# Sheet2.net
KiCad netlist of a schematic drawn in Altium Designer
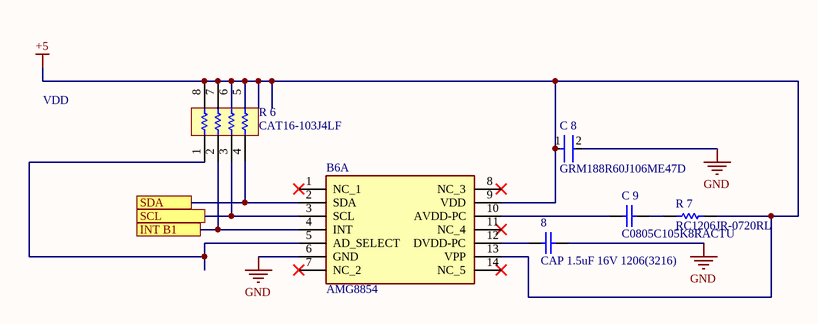
[diagram p0: Sheet2.SchDoc]

(export (version "E")
  (design (tool "Eeschema 10.0.6"))
  (components
    (comp (ref "8")
      (value "CAP 1.5uF 16V 1206(3216)")
      (footprint "CAPC1206(3216)190_M")
      (description "CAP 1.5uF 16V ±10% 1206 (3216 Metric) Thickness 1.9mm SMD")
      (fields (field (name "TOLERANCE") "Â±10%"))
      (libsource (lib "Altium Content Vault") (part "CAP"))
    )
    (comp (ref "B6")
      (value "AMG8854")
      (footprint "AMG8854:AMG8854")
      (fields (field (name "MOUSER PART NUMBER") "667-AMG8854"))
      (libsource (lib "AMG8854") (part "AMG8854"))
    )
    (comp (ref "C 8")
      (value "GRM188R60J106ME47D")
      (footprint "FP-GRM188-0_1-e0_2_0_55-IPC_A")
      (description "Chip Multilayer Ceramic Capacitors for General Purpose, 0603, 10uF, X5R, 15%, 20%, 6.3V")
      (fields (field (name "VOLTAGE") "6.3V") (field (name "TOLERANCE") "20%"))
      (libsource (lib "Altium Content Vault") (part "02cd4be3c70576c341d710602a673aa"))
    )
    (comp (ref "C 9")
      (value "C0805C105K8RACTU")
      (footprint "CAPC2013X100X50ML20T25")
      (fields (field (name "MANUFACTURER") "Kemet"))
      (libsource (lib "Altium Content Vault") (part "CAP"))
    )
    (comp (ref "R 6")
      (value "CAT16-103J4LF")
      (footprint "BOUR-CAT16-103J4LF_L")
      (fields (field (name "MANUFACTURER") "Bourns") (field (name "TOLERANCE") "±5%"))
      (libsource (lib "Altium Content Vault") (part "RES-P-8"))
    )
    (comp (ref "R 7")
      (value "RC1206JR-0720RL")
      (footprint "RESC3116X65X40NL10T20")
      (fields (field (name "MANUFACTURER") "Yageo"))
      (libsource (lib "Altium Content Vault") (part "RES"))
    )
  )
  (nets
    (net (code "1") (name "+5") (class "Default")
      (node (ref "B6") (pin "13") (pinfunction "VPP_13") (pintype "passive"))
      (node (ref "B6") (pin "9") (pinfunction "VDD_9") (pintype "passive"))
      (node (ref "C 8") (pin "1") (pinfunction "1_1") (pintype "passive"))
      (node (ref "R 6") (pin "5") (pinfunction "5_5") (pintype "passive"))
      (node (ref "R 6") (pin "6") (pinfunction "6_6") (pintype "passive"))
      (node (ref "R 6") (pin "7") (pinfunction "7_7") (pintype "passive"))
      (node (ref "R 6") (pin "8") (pinfunction "8_8") (pintype "passive"))
      (node (ref "R 7") (pin "2") (pinfunction "2_2") (pintype "passive"))
    )
    (net (code "2") (name "/INT B1") (class "Default")
      (node (ref "B6") (pin "4") (pinfunction "INT_4") (pintype "passive"))
      (node (ref "R 6") (pin "2") (pinfunction "2_2") (pintype "passive"))
    )
    (net (code "3") (name "/SCL") (class "Default")
      (node (ref "B6") (pin "3") (pinfunction "SCL_3") (pintype "passive"))
      (node (ref "R 6") (pin "3") (pinfunction "3_3") (pintype "passive"))
    )
    (net (code "4") (name "/SDA") (class "Default")
      (node (ref "B6") (pin "2") (pinfunction "SDA_2") (pintype "passive"))
      (node (ref "R 6") (pin "4") (pinfunction "4_4") (pintype "passive"))
    )
    (net (code "5") (name "GND") (class "Default")
      (node (ref "8") (pin "2") (pinfunction "2_2") (pintype "passive"))
      (node (ref "B6") (pin "6") (pinfunction "GND_6") (pintype "passive"))
      (node (ref "C 8") (pin "2") (pinfunction "2_2") (pintype "passive"))
    )
    (net (code "6") (name "Net-(B6-AD_SELECT)") (class "Default")
      (node (ref "B6") (pin "5") (pinfunction "AD_SELECT_5") (pintype "passive"))
      (node (ref "R 6") (pin "1") (pinfunction "1_1") (pintype "passive"))
    )
    (net (code "7") (name "Net-(B6-AVDD-PC)") (class "Default")
      (node (ref "B6") (pin "10") (pinfunction "AVDD-PC_10") (pintype "passive"))
      (node (ref "C 9") (pin "1") (pinfunction "1_1") (pintype "passive"))
    )
    (net (code "8") (name "Net-(B6-DVDD-PC)") (class "Default")
      (node (ref "8") (pin "1") (pinfunction "1_1") (pintype "passive"))
      (node (ref "B6") (pin "12") (pinfunction "DVDD-PC_12") (pintype "passive"))
    )
    (net (code "9") (name "Net-(C 9-Pad2)") (class "Default")
      (node (ref "C 9") (pin "2") (pinfunction "2_2") (pintype "passive"))
      (node (ref "R 7") (pin "1") (pinfunction "1_1") (pintype "passive"))
    )
    (net (code "10") (name "unconnected-(B6-NC_1-Pad1)") (class "Default")
      (node (ref "B6") (pin "1") (pinfunction "NC_1_1") (pintype "passive+no_connect"))
    )
    (net (code "11") (name "unconnected-(B6-NC_2-Pad7)") (class "Default")
      (node (ref "B6") (pin "7") (pinfunction "NC_2_7") (pintype "passive+no_connect"))
    )
    (net (code "12") (name "unconnected-(B6-NC_3-Pad8)") (class "Default")
      (node (ref "B6") (pin "8") (pinfunction "NC_3_8") (pintype "passive+no_connect"))
    )
    (net (code "13") (name "unconnected-(B6-NC_4-Pad11)") (class "Default")
      (node (ref "B6") (pin "11") (pinfunction "NC_4_11") (pintype "passive+no_connect"))
    )
    (net (code "14") (name "unconnected-(B6-NC_5-Pad14)") (class "Default")
      (node (ref "B6") (pin "14") (pinfunction "NC_5_14") (pintype "passive+no_connect"))
    )
  )
)
